# AirCraft_V1_0.net
KiCad netlist of a schematic drawn in Altium Designer
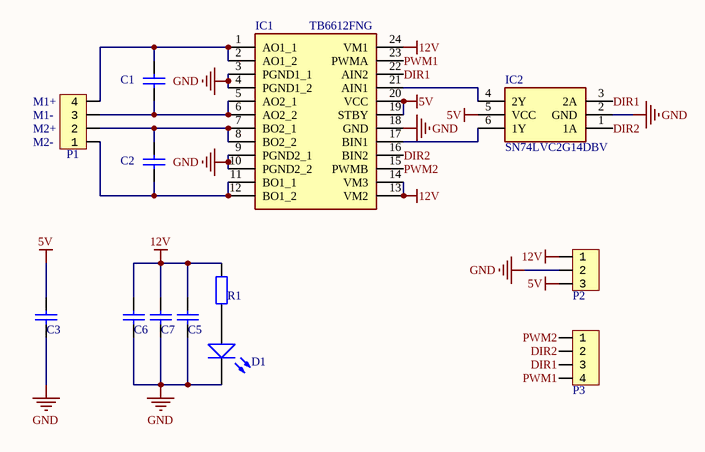
[diagram p0: AirCraft_V1.0.SchDoc]

(export (version "E")
  (design (tool "Eeschema 10.0.6"))
  (components
    (comp (ref "C1")
      (value "100nF")
      (footprint "CAP-0603")
      (description "贴片电容")
      (libsource (lib "Power_Lib_Altium") (part "CAP"))
    )
    (comp (ref "C2")
      (value "100nF")
      (footprint "CAP-0603")
      (description "贴片电容")
      (libsource (lib "Power_Lib_Altium") (part "CAP"))
    )
    (comp (ref "C3")
      (value "100nF")
      (footprint "CAP-0603")
      (description "贴片电容")
      (libsource (lib "Power_Lib_Altium") (part "CAP"))
    )
    (comp (ref "C5")
      (value "100nF")
      (footprint "CAP-0603")
      (description "贴片电容")
      (libsource (lib "Power_Lib_Altium") (part "CAP"))
    )
    (comp (ref "C6")
      (value "47uF")
      (footprint "CAP-1206")
      (description "贴片电容")
      (libsource (lib "Power_Lib_Altium") (part "CAP"))
    )
    (comp (ref "C7")
      (value "47uF")
      (footprint "CAP-1206")
      (description "贴片电容")
      (libsource (lib "Power_Lib_Altium") (part "CAP"))
    )
    (comp (ref "D1")
      (value "RED")
      (footprint "LED-0603")
      (description "发光二极管")
      (libsource (lib "Power_Lib_Altium") (part "LED"))
    )
    (comp (ref "IC1")
      (value "TB6612FNG")
      (footprint "SSOP24")
      (description "集成电机驱动芯片")
      (fields
        (field (name "MANUFACTURER_PART_NUMBER") "TB6612FNG(O,EL)")
        (field (name "MOUSER PART NUMBER") "757-TB6612FNG(O,EL)")
      )
      (libsource (lib "Power_Lib_Altium") (part "TB6612FNG"))
    )
    (comp (ref "IC2")
      (value "SN74LVC2G14DBV")
      (footprint "SOT-23-6")
      (description "变换器")
      (fields
        (field (name "MANUFACTURER_PART_NUMBER") "SN74LVC2G14DBVR")
        (field (name "MOUSER PART NUMBER") "595-SN74LVC2G14DBVR")
      )
      (libsource (lib "Power_Lib_Altium") (part "SN74LVC2G14DBV"))
    )
    (comp (ref "P1")
      (value "HDR1x4_2.54")
      (footprint "HDR1X4_2.54_90")
      (description "Header")
      (libsource (lib "") (part "HDR1x4_2.54_1"))
    )
    (comp (ref "P2")
      (value "XH-3AW")
      (footprint "XH_3")
      (description "Header")
      (libsource (lib "Power_Lib_Altium") (part "HDR1x3_2.54"))
    )
    (comp (ref "P3")
      (value "XH-4AW")
      (footprint "XH_4")
      (description "Header")
      (libsource (lib "Power_Lib_Altium") (part "HDR1x4_2.54"))
    )
    (comp (ref "R1")
      (value "4.7k")
      (footprint "R-0603")
      (description "贴片电阻")
      (libsource (lib "Power_Lib_Altium") (part "RES"))
    )
  )
  (nets
    (net (code "1") (name "/DIR1") (class "Default")
      (node (ref "IC1") (pin "22") (pinfunction "AIN2_22") (pintype "passive"))
      (node (ref "IC2") (pin "3") (pinfunction "2A_3") (pintype "passive"))
      (node (ref "P3") (pin "3") (pinfunction "3_3") (pintype "passive"))
    )
    (net (code "2") (name "/DIR2") (class "Default")
      (node (ref "IC1") (pin "16") (pinfunction "BIN2_16") (pintype "passive"))
      (node (ref "IC2") (pin "1") (pinfunction "1A_1") (pintype "passive"))
      (node (ref "P3") (pin "2") (pinfunction "2_2") (pintype "passive"))
    )
    (net (code "3") (name "/PWM1") (class "Default")
      (node (ref "IC1") (pin "23") (pinfunction "PWMA_23") (pintype "passive"))
      (node (ref "P3") (pin "4") (pinfunction "4_4") (pintype "passive"))
    )
    (net (code "4") (name "/PWM2") (class "Default")
      (node (ref "IC1") (pin "15") (pinfunction "PWMB_15") (pintype "passive"))
      (node (ref "P3") (pin "1") (pinfunction "1_1") (pintype "passive"))
    )
    (net (code "5") (name "5V") (class "Default")
      (node (ref "C3") (pin "2") (pinfunction "2_2") (pintype "passive"))
      (node (ref "IC1") (pin "19") (pinfunction "STBY_19") (pintype "passive"))
      (node (ref "IC1") (pin "20") (pinfunction "VCC_20") (pintype "passive"))
      (node (ref "IC2") (pin "5") (pinfunction "VCC_5") (pintype "passive"))
      (node (ref "P2") (pin "3") (pinfunction "3_3") (pintype "passive"))
    )
    (net (code "6") (name "12V") (class "Default")
      (node (ref "C5") (pin "2") (pinfunction "2_2") (pintype "passive"))
      (node (ref "C6") (pin "2") (pinfunction "2_2") (pintype "passive"))
      (node (ref "C7") (pin "2") (pinfunction "2_2") (pintype "passive"))
      (node (ref "IC1") (pin "13") (pinfunction "VM2_13") (pintype "passive"))
      (node (ref "IC1") (pin "14") (pinfunction "VM3_14") (pintype "passive"))
      (node (ref "IC1") (pin "24") (pinfunction "VM1_24") (pintype "passive"))
      (node (ref "P2") (pin "1") (pinfunction "1_1") (pintype "passive"))
      (node (ref "R1") (pin "2") (pinfunction "2_2") (pintype "passive"))
    )
    (net (code "7") (name "GND") (class "Default")
      (node (ref "C3") (pin "1") (pinfunction "1_1") (pintype "passive"))
      (node (ref "C5") (pin "1") (pinfunction "1_1") (pintype "passive"))
      (node (ref "C6") (pin "1") (pinfunction "1_1") (pintype "passive"))
      (node (ref "C7") (pin "1") (pinfunction "1_1") (pintype "passive"))
      (node (ref "D1") (pin "K") (pinfunction "K_K") (pintype "passive"))
      (node (ref "IC1") (pin "10") (pinfunction "PGND2_2_10") (pintype "passive"))
      (node (ref "IC1") (pin "18") (pinfunction "GND_18") (pintype "passive"))
      (node (ref "IC1") (pin "3") (pinfunction "PGND1_1_3") (pintype "passive"))
      (node (ref "IC1") (pin "4") (pinfunction "PGND1_2_4") (pintype "passive"))
      (node (ref "IC1") (pin "9") (pinfunction "PGND2_1_9") (pintype "passive"))
      (node (ref "IC2") (pin "2") (pinfunction "GND_2") (pintype "passive"))
      (node (ref "P2") (pin "2") (pinfunction "2_2") (pintype "passive"))
    )
    (net (code "8") (name "Net-(D1-PadA)") (class "Default")
      (node (ref "D1") (pin "A") (pinfunction "A_A") (pintype "passive"))
      (node (ref "R1") (pin "1") (pinfunction "1_1") (pintype "passive"))
    )
    (net (code "9") (name "Net-(IC1-AIN1)") (class "Default")
      (node (ref "IC1") (pin "21") (pinfunction "AIN1_21") (pintype "passive"))
      (node (ref "IC2") (pin "4") (pinfunction "2Y_4") (pintype "passive"))
    )
    (net (code "10") (name "Net-(IC1-AO1_1)") (class "Default")
      (node (ref "C1") (pin "2") (pinfunction "2_2") (pintype "passive"))
      (node (ref "IC1") (pin "1") (pinfunction "AO1_1_1") (pintype "passive"))
      (node (ref "IC1") (pin "2") (pinfunction "AO1_2_2") (pintype "passive"))
      (node (ref "P1") (pin "4") (pinfunction "4_4") (pintype "passive"))
    )
    (net (code "11") (name "Net-(IC1-AO2_1)") (class "Default")
      (node (ref "C1") (pin "1") (pinfunction "1_1") (pintype "passive"))
      (node (ref "IC1") (pin "5") (pinfunction "AO2_1_5") (pintype "passive"))
      (node (ref "IC1") (pin "6") (pinfunction "AO2_2_6") (pintype "passive"))
      (node (ref "P1") (pin "3") (pinfunction "3_3") (pintype "passive"))
    )
    (net (code "12") (name "Net-(IC1-BIN1)") (class "Default")
      (node (ref "IC1") (pin "17") (pinfunction "BIN1_17") (pintype "passive"))
      (node (ref "IC2") (pin "6") (pinfunction "1Y_6") (pintype "passive"))
    )
    (net (code "13") (name "Net-(IC1-BO1_1)") (class "Default")
      (node (ref "C2") (pin "1") (pinfunction "1_1") (pintype "passive"))
      (node (ref "IC1") (pin "11") (pinfunction "BO1_1_11") (pintype "passive"))
      (node (ref "IC1") (pin "12") (pinfunction "BO1_2_12") (pintype "passive"))
      (node (ref "P1") (pin "1") (pinfunction "1_1") (pintype "passive"))
    )
    (net (code "14") (name "Net-(IC1-BO2_1)") (class "Default")
      (node (ref "C2") (pin "2") (pinfunction "2_2") (pintype "passive"))
      (node (ref "IC1") (pin "7") (pinfunction "BO2_1_7") (pintype "passive"))
      (node (ref "IC1") (pin "8") (pinfunction "BO2_2_8") (pintype "passive"))
      (node (ref "P1") (pin "2") (pinfunction "2_2") (pintype "passive"))
    )
  )
)
